# dmo.net
KiCad netlist of a schematic drawn in EAGLE
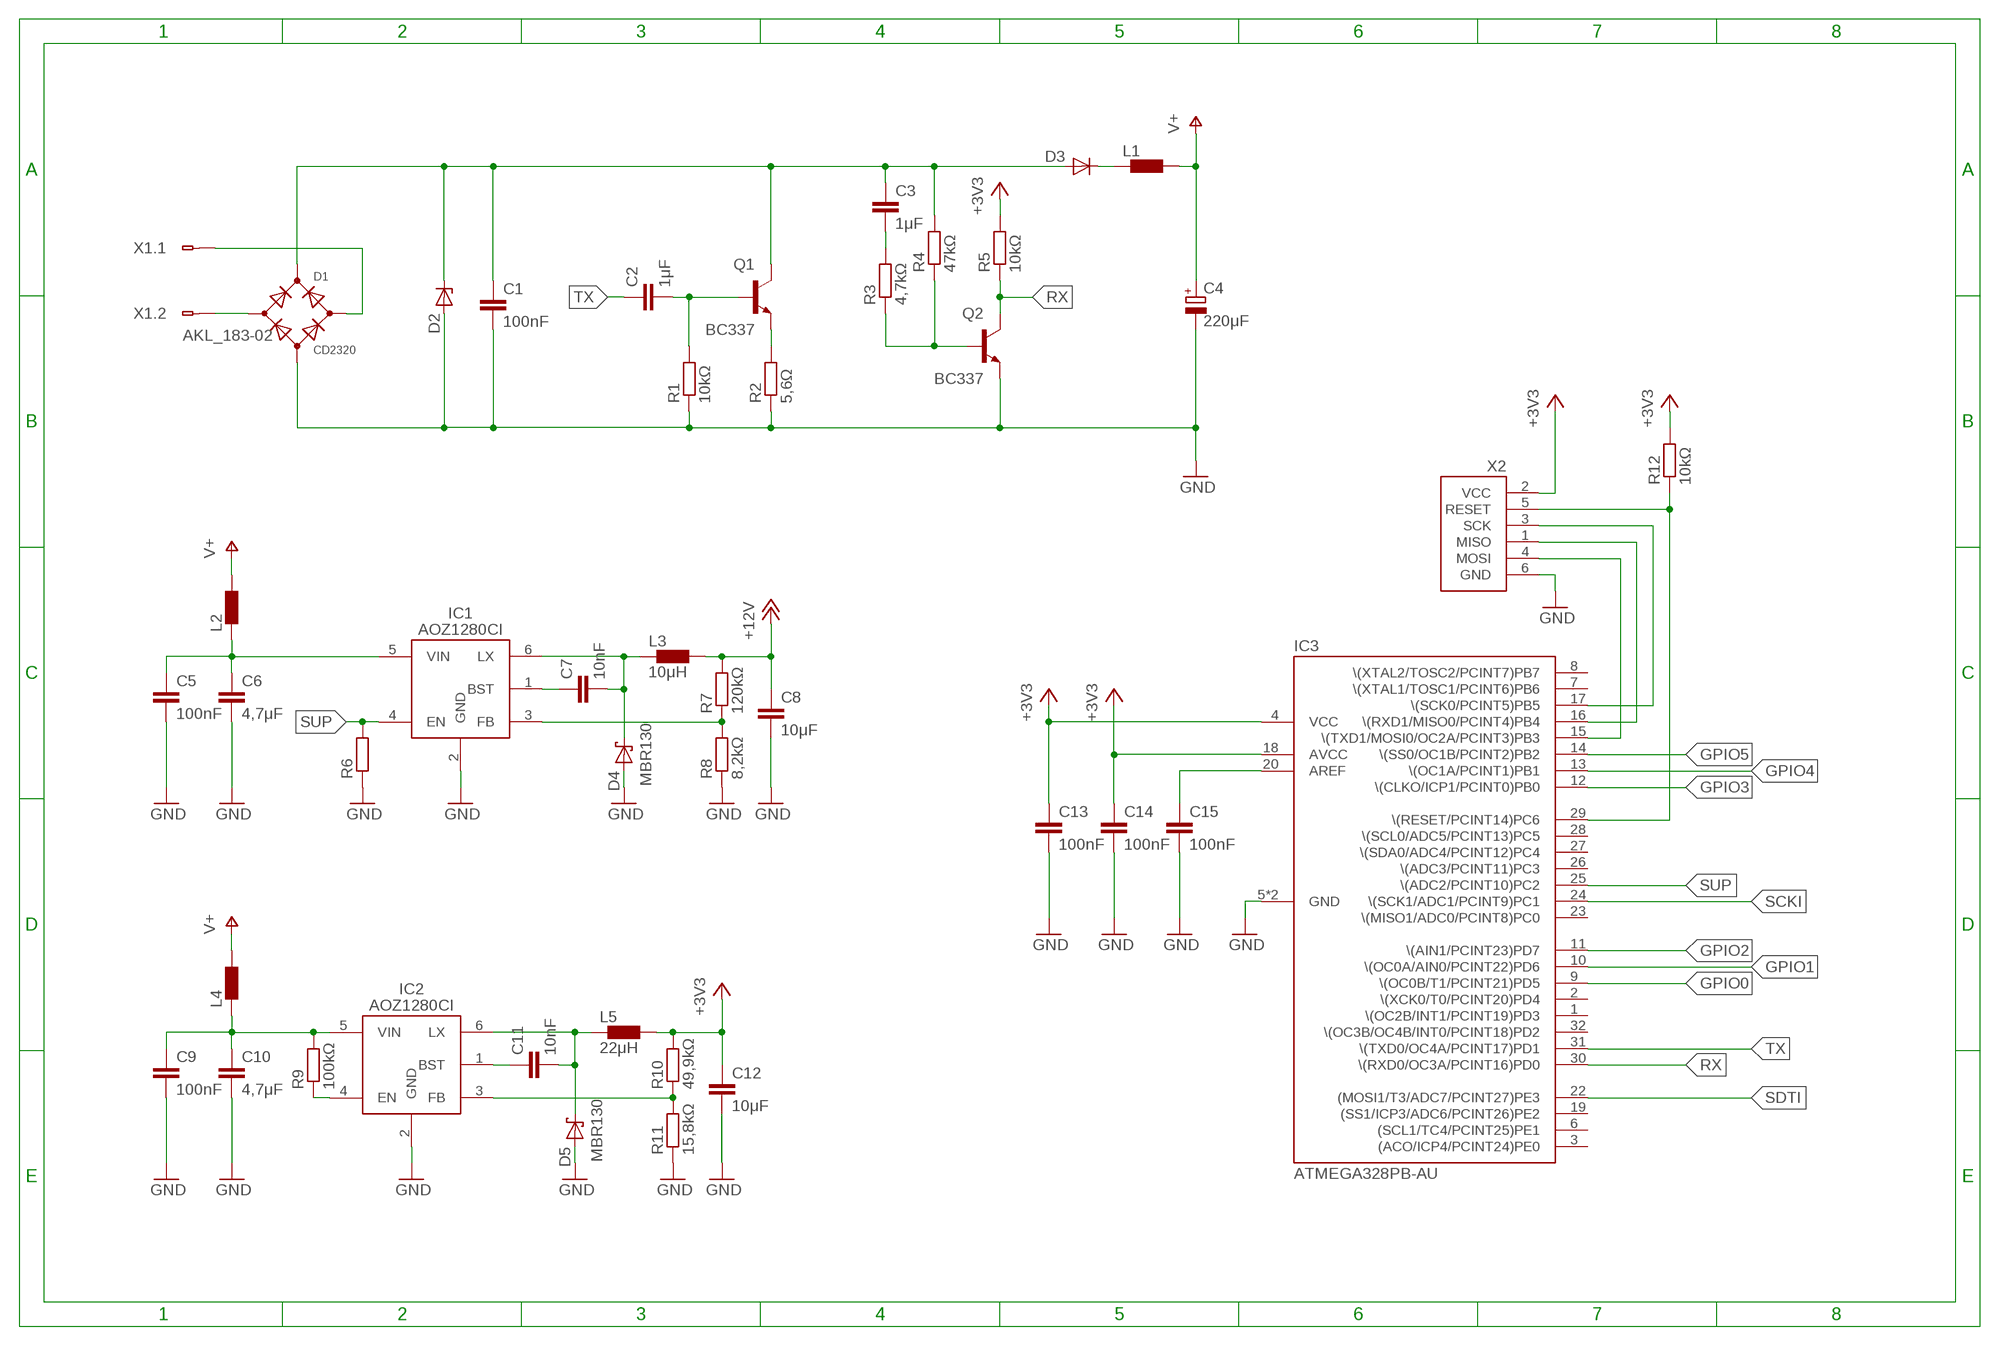
[diagram p0: schematic, sheet 1]

(export (version "E")
  (design (tool "Eeschema 10.0.6"))
  (components
    (comp (ref "C1")
      (value "100nF")
      (footprint "eagle-import:CHIP_1206")
      (libsource (lib "eagle-import") (part "C_1206"))
    )
    (comp (ref "C2")
      (value "1μF")
      (footprint "eagle-import:CHIP_1206")
      (libsource (lib "eagle-import") (part "C_1206"))
    )
    (comp (ref "C3")
      (value "1μF")
      (footprint "eagle-import:CHIP_1206")
      (libsource (lib "eagle-import") (part "C_1206"))
    )
    (comp (ref "C4")
      (value "220μF")
      (footprint "eagle-import:E5-13")
      (libsource (lib "eagle-import") (part "C_EL_E5-13"))
    )
    (comp (ref "C5")
      (value "100nF")
      (footprint "eagle-import:CHIP_0805")
      (libsource (lib "eagle-import") (part "C_0805"))
    )
    (comp (ref "C6")
      (value "4,7μF")
      (footprint "eagle-import:CHIP_1206")
      (libsource (lib "eagle-import") (part "C_1206"))
    )
    (comp (ref "C7")
      (value "10nF")
      (footprint "eagle-import:CHIP_0603")
      (libsource (lib "eagle-import") (part "C_0603"))
    )
    (comp (ref "C8")
      (value "10μF")
      (footprint "eagle-import:CHIP_1206")
      (libsource (lib "eagle-import") (part "C_1206"))
    )
    (comp (ref "C9")
      (value "100nF")
      (footprint "eagle-import:CHIP_0805")
      (libsource (lib "eagle-import") (part "C_0805"))
    )
    (comp (ref "C10")
      (value "4,7μF")
      (footprint "eagle-import:CHIP_1206")
      (libsource (lib "eagle-import") (part "C_1206"))
    )
    (comp (ref "C11")
      (value "10nF")
      (footprint "eagle-import:CHIP_0603")
      (libsource (lib "eagle-import") (part "C_0603"))
    )
    (comp (ref "C12")
      (value "10μF")
      (footprint "eagle-import:CHIP_1206")
      (libsource (lib "eagle-import") (part "C_1206"))
    )
    (comp (ref "C13")
      (value "100nF")
      (footprint "eagle-import:CHIP_0603")
      (libsource (lib "eagle-import") (part "C_0603"))
    )
    (comp (ref "C14")
      (value "100nF")
      (footprint "eagle-import:CHIP_0603")
      (libsource (lib "eagle-import") (part "C_0603"))
    )
    (comp (ref "C15")
      (value "100nF")
      (footprint "eagle-import:CHIP_0603")
      (libsource (lib "eagle-import") (part "C_0603"))
    )
    (comp (ref "D1")
      (value "CD2320")
      (footprint "eagle-import:2320")
      (libsource (lib "eagle-import") (part "CD2320"))
    )
    (comp (ref "D2")
      (value "Z-DIODE-SOD123")
      (footprint "eagle-import:SOD123")
      (libsource (lib "eagle-import") (part "Z-DIODE-SOD123"))
    )
    (comp (ref "D3")
      (value "DIODE-SOD123")
      (footprint "eagle-import:SOD123")
      (libsource (lib "eagle-import") (part "DIODE-SOD123"))
    )
    (comp (ref "D4")
      (value "MBR130")
      (footprint "eagle-import:SOD123")
      (libsource (lib "eagle-import") (part "SHOTKY-DIODE-SOD123"))
    )
    (comp (ref "D5")
      (value "MBR130")
      (footprint "eagle-import:SOD123")
      (libsource (lib "eagle-import") (part "SHOTKY-DIODE-SOD123"))
    )
    (comp (ref "IC1")
      (value "AOZ1280CI")
      (footprint "eagle-import:SOT23-6_095")
      (libsource (lib "eagle-import") (part "AOZ1280CI"))
    )
    (comp (ref "IC2")
      (value "AOZ1280CI")
      (footprint "eagle-import:SOT23-6_095")
      (libsource (lib "eagle-import") (part "AOZ1280CI"))
    )
    (comp (ref "IC3")
      (value "ATMEGA328PB-AU")
      (footprint "eagle-import:QFP32_08")
      (libsource (lib "eagle-import") (part "ATMEGA8PB-AU32"))
    )
    (comp (ref "L1")
      (value "L_0805")
      (footprint "eagle-import:CHIP_0805")
      (libsource (lib "eagle-import") (part "L_0805"))
    )
    (comp (ref "L2")
      (value "L_0805")
      (footprint "eagle-import:CHIP_0805")
      (libsource (lib "eagle-import") (part "L_0805"))
    )
    (comp (ref "L3")
      (value "10μH")
      (footprint "eagle-import:CHIP_1210")
      (libsource (lib "eagle-import") (part "L_1210"))
    )
    (comp (ref "L4")
      (value "L_0805")
      (footprint "eagle-import:CHIP_0805")
      (libsource (lib "eagle-import") (part "L_0805"))
    )
    (comp (ref "L5")
      (value "22μH")
      (footprint "eagle-import:CHIP_0805")
      (libsource (lib "eagle-import") (part "L_0805"))
    )
    (comp (ref "Q1")
      (value "BC337")
      (footprint "eagle-import:SOT23")
      (libsource (lib "eagle-import") (part "NPN-SOT23-BEC"))
    )
    (comp (ref "Q2")
      (value "BC337")
      (footprint "eagle-import:SOT23")
      (libsource (lib "eagle-import") (part "NPN-SOT23-BEC"))
    )
    (comp (ref "R1")
      (value "10kΩ")
      (footprint "eagle-import:CHIP_0603")
      (libsource (lib "eagle-import") (part "R_0603"))
    )
    (comp (ref "R2")
      (value "5,6Ω")
      (footprint "eagle-import:CHIP_1206")
      (libsource (lib "eagle-import") (part "R_1206"))
    )
    (comp (ref "R3")
      (value "4,7kΩ")
      (footprint "eagle-import:CHIP_0603")
      (libsource (lib "eagle-import") (part "R_0603"))
    )
    (comp (ref "R4")
      (value "47kΩ")
      (footprint "eagle-import:CHIP_0603")
      (libsource (lib "eagle-import") (part "R_0603"))
    )
    (comp (ref "R5")
      (value "10kΩ")
      (footprint "eagle-import:CHIP_0603")
      (libsource (lib "eagle-import") (part "R_0603"))
    )
    (comp (ref "R6")
      (value "R_0603")
      (footprint "eagle-import:CHIP_0603")
      (libsource (lib "eagle-import") (part "R_0603"))
    )
    (comp (ref "R7")
      (value "120kΩ")
      (footprint "eagle-import:CHIP_0603")
      (libsource (lib "eagle-import") (part "R_0603"))
    )
    (comp (ref "R8")
      (value "8,2kΩ")
      (footprint "eagle-import:CHIP_0603")
      (libsource (lib "eagle-import") (part "R_0603"))
    )
    (comp (ref "R9")
      (value "100kΩ")
      (footprint "eagle-import:CHIP_0603")
      (libsource (lib "eagle-import") (part "R_0603"))
    )
    (comp (ref "R10")
      (value "49,9kΩ")
      (footprint "eagle-import:CHIP_0603")
      (libsource (lib "eagle-import") (part "R_0603"))
    )
    (comp (ref "R11")
      (value "15,8kΩ")
      (footprint "eagle-import:CHIP_0603")
      (libsource (lib "eagle-import") (part "R_0603"))
    )
    (comp (ref "R12")
      (value "10kΩ")
      (footprint "eagle-import:CHIP_0603")
      (libsource (lib "eagle-import") (part "R_0603"))
    )
    (comp (ref "X1")
      (value "AKL_183-02")
      (footprint "eagle-import:AKL_183-02")
      (libsource (lib "eagle-import") (part "AKL_183-02"))
    )
    (comp (ref "X2")
      (value "ISP-AVR6")
      (footprint "eagle-import:ML6")
      (libsource (lib "eagle-import") (part "ISP-AVR6"))
    )
  )
  (nets
    (net (code "1") (name "+3V3") (class "Default")
      (node (ref "C12") (pin "1") (pinfunction "1_1") (pintype "passive"))
      (node (ref "C13") (pin "1") (pinfunction "1_1") (pintype "passive"))
      (node (ref "C14") (pin "1") (pinfunction "1_1") (pintype "passive"))
      (node (ref "IC3") (pin "18") (pinfunction "AVCC_18") (pintype "power_in"))
      (node (ref "IC3") (pin "4") (pinfunction "VCC_4") (pintype "power_in"))
      (node (ref "L5") (pin "1") (pinfunction "1_1") (pintype "passive"))
      (node (ref "R10") (pin "2") (pinfunction "2_2") (pintype "passive"))
      (node (ref "R12") (pin "2") (pinfunction "2_2") (pintype "passive"))
      (node (ref "R5") (pin "2") (pinfunction "2_2") (pintype "passive"))
      (node (ref "X2") (pin "2") (pinfunction "VCC_2") (pintype "power_in"))
    )
    (net (code "2") (name "+12V") (class "Default")
      (node (ref "C8") (pin "1") (pinfunction "1_1") (pintype "passive"))
      (node (ref "L3") (pin "1") (pinfunction "1_1") (pintype "passive"))
      (node (ref "R7") (pin "2") (pinfunction "2_2") (pintype "passive"))
    )
    (net (code "3") (name "GND") (class "Default")
      (node (ref "C1") (pin "2") (pinfunction "2_2") (pintype "passive"))
      (node (ref "C10") (pin "2") (pinfunction "2_2") (pintype "passive"))
      (node (ref "C12") (pin "2") (pinfunction "2_2") (pintype "passive"))
      (node (ref "C13") (pin "2") (pinfunction "2_2") (pintype "passive"))
      (node (ref "C14") (pin "2") (pinfunction "2_2") (pintype "passive"))
      (node (ref "C15") (pin "2") (pinfunction "2_2") (pintype "passive"))
      (node (ref "C4") (pin "-") (pinfunction "-_-") (pintype "passive"))
      (node (ref "C5") (pin "2") (pinfunction "2_2") (pintype "passive"))
      (node (ref "C6") (pin "2") (pinfunction "2_2") (pintype "passive"))
      (node (ref "C8") (pin "2") (pinfunction "2_2") (pintype "passive"))
      (node (ref "C9") (pin "2") (pinfunction "2_2") (pintype "passive"))
      (node (ref "D1") (pin "-") (pinfunction "-_-") (pintype "passive"))
      (node (ref "D2") (pin "A") (pinfunction "A_A") (pintype "passive"))
      (node (ref "D4") (pin "A") (pinfunction "A_A") (pintype "passive"))
      (node (ref "D5") (pin "A") (pinfunction "A_A") (pintype "passive"))
      (node (ref "IC1") (pin "2") (pinfunction "GND_2") (pintype "power_in"))
      (node (ref "IC2") (pin "2") (pinfunction "GND_2") (pintype "power_in"))
      (node (ref "IC3") (pin "21") (pinfunction "GND_21") (pintype "power_in"))
      (node (ref "IC3") (pin "5") (pinfunction "GND_5") (pintype "power_in"))
      (node (ref "Q2") (pin "2") (pinfunction "E_2") (pintype "passive"))
      (node (ref "R1") (pin "1") (pinfunction "1_1") (pintype "passive"))
      (node (ref "R11") (pin "1") (pinfunction "1_1") (pintype "passive"))
      (node (ref "R2") (pin "1") (pinfunction "1_1") (pintype "passive"))
      (node (ref "R6") (pin "1") (pinfunction "1_1") (pintype "passive"))
      (node (ref "R8") (pin "1") (pinfunction "1_1") (pintype "passive"))
      (node (ref "X2") (pin "6") (pinfunction "GND_6") (pintype "power_in"))
    )
    (net (code "4") (name "GPIO0") (class "Default")
      (node (ref "IC3") (pin "9") (pinfunction "\\(OC0B/T1/PCINT21)PD5_9") (pintype "bidirectional"))
    )
    (net (code "5") (name "GPIO1") (class "Default")
      (node (ref "IC3") (pin "10") (pinfunction "\\(OC0A/AIN0/PCINT22)PD6_10") (pintype "bidirectional"))
    )
    (net (code "6") (name "GPIO2") (class "Default")
      (node (ref "IC3") (pin "11") (pinfunction "\\(AIN1/PCINT23)PD7_11") (pintype "bidirectional"))
    )
    (net (code "7") (name "GPIO3") (class "Default")
      (node (ref "IC3") (pin "12") (pinfunction "\\(CLKO/ICP1/PCINT0)PB0_12") (pintype "bidirectional"))
    )
    (net (code "8") (name "GPIO4") (class "Default")
      (node (ref "IC3") (pin "13") (pinfunction "\\(OC1A/PCINT1)PB1_13") (pintype "bidirectional"))
    )
    (net (code "9") (name "GPIO5") (class "Default")
      (node (ref "IC3") (pin "14") (pinfunction "\\(SS0/OC1B/PCINT2)PB2_14") (pintype "bidirectional"))
    )
    (net (code "10") (name "Net-(C3-Pad2)") (class "Default")
      (node (ref "C3") (pin "2") (pinfunction "2_2") (pintype "passive"))
      (node (ref "R3") (pin "2") (pinfunction "2_2") (pintype "passive"))
    )
    (net (code "11") (name "Net-(D3-PadK)") (class "Default")
      (node (ref "D3") (pin "K") (pinfunction "K_K") (pintype "passive"))
      (node (ref "L1") (pin "2") (pinfunction "2_2") (pintype "passive"))
    )
    (net (code "12") (name "Net-(IC1-BST)") (class "Default")
      (node (ref "C7") (pin "1") (pinfunction "1_1") (pintype "passive"))
      (node (ref "IC1") (pin "1") (pinfunction "BST_1") (pintype "bidirectional"))
    )
    (net (code "13") (name "Net-(IC1-FB)") (class "Default")
      (node (ref "IC1") (pin "3") (pinfunction "FB_3") (pintype "input"))
      (node (ref "R7") (pin "1") (pinfunction "1_1") (pintype "passive"))
      (node (ref "R8") (pin "2") (pinfunction "2_2") (pintype "passive"))
    )
    (net (code "14") (name "Net-(IC1-LX)") (class "Default")
      (node (ref "C7") (pin "2") (pinfunction "2_2") (pintype "passive"))
      (node (ref "D4") (pin "K") (pinfunction "K_K") (pintype "passive"))
      (node (ref "IC1") (pin "6") (pinfunction "LX_6") (pintype "output"))
      (node (ref "L3") (pin "2") (pinfunction "2_2") (pintype "passive"))
    )
    (net (code "15") (name "Net-(IC1-VIN)") (class "Default")
      (node (ref "C5") (pin "1") (pinfunction "1_1") (pintype "passive"))
      (node (ref "C6") (pin "1") (pinfunction "1_1") (pintype "passive"))
      (node (ref "IC1") (pin "5") (pinfunction "VIN_5") (pintype "power_in"))
      (node (ref "L2") (pin "2") (pinfunction "2_2") (pintype "passive"))
    )
    (net (code "16") (name "Net-(IC2-BST)") (class "Default")
      (node (ref "C11") (pin "1") (pinfunction "1_1") (pintype "passive"))
      (node (ref "IC2") (pin "1") (pinfunction "BST_1") (pintype "bidirectional"))
    )
    (net (code "17") (name "Net-(IC2-EN)") (class "Default")
      (node (ref "IC2") (pin "4") (pinfunction "EN_4") (pintype "input"))
      (node (ref "R9") (pin "1") (pinfunction "1_1") (pintype "passive"))
    )
    (net (code "18") (name "Net-(IC2-FB)") (class "Default")
      (node (ref "IC2") (pin "3") (pinfunction "FB_3") (pintype "input"))
      (node (ref "R10") (pin "1") (pinfunction "1_1") (pintype "passive"))
      (node (ref "R11") (pin "2") (pinfunction "2_2") (pintype "passive"))
    )
    (net (code "19") (name "Net-(IC2-LX)") (class "Default")
      (node (ref "C11") (pin "2") (pinfunction "2_2") (pintype "passive"))
      (node (ref "D5") (pin "K") (pinfunction "K_K") (pintype "passive"))
      (node (ref "IC2") (pin "6") (pinfunction "LX_6") (pintype "output"))
      (node (ref "L5") (pin "2") (pinfunction "2_2") (pintype "passive"))
    )
    (net (code "20") (name "Net-(IC2-VIN)") (class "Default")
      (node (ref "C10") (pin "1") (pinfunction "1_1") (pintype "passive"))
      (node (ref "C9") (pin "1") (pinfunction "1_1") (pintype "passive"))
      (node (ref "IC2") (pin "5") (pinfunction "VIN_5") (pintype "power_in"))
      (node (ref "L4") (pin "2") (pinfunction "2_2") (pintype "passive"))
      (node (ref "R9") (pin "2") (pinfunction "2_2") (pintype "passive"))
    )
    (net (code "21") (name "Net-(IC3-AREF)") (class "Default")
      (node (ref "C15") (pin "1") (pinfunction "1_1") (pintype "passive"))
      (node (ref "IC3") (pin "20") (pinfunction "AREF_20") (pintype "passive"))
    )
    (net (code "22") (name "Net-(IC3-\\(RESET{slash}PCINT14)PC6)") (class "Default")
      (node (ref "IC3") (pin "29") (pinfunction "\\(RESET/PCINT14)PC6_29") (pintype "bidirectional"))
      (node (ref "R12") (pin "1") (pinfunction "1_1") (pintype "passive"))
      (node (ref "X2") (pin "5") (pinfunction "RESET_5") (pintype "passive"))
    )
    (net (code "23") (name "Net-(IC3-\\(RXD1{slash}MISO0{slash}PCINT4)PB4)") (class "Default")
      (node (ref "IC3") (pin "16") (pinfunction "\\(RXD1/MISO0/PCINT4)PB4_16") (pintype "bidirectional"))
      (node (ref "X2") (pin "1") (pinfunction "MISO_1") (pintype "passive"))
    )
    (net (code "24") (name "Net-(IC3-\\(SCK0{slash}PCINT5)PB5)") (class "Default")
      (node (ref "IC3") (pin "17") (pinfunction "\\(SCK0/PCINT5)PB5_17") (pintype "bidirectional"))
      (node (ref "X2") (pin "3") (pinfunction "SCK_3") (pintype "passive"))
    )
    (net (code "25") (name "Net-(IC3-\\(TXD1{slash}MOSI0{slash}OC2A{slash}PCINT3)PB3)") (class "Default")
      (node (ref "IC3") (pin "15") (pinfunction "\\(TXD1/MOSI0/OC2A/PCINT3)PB3_15") (pintype "bidirectional"))
      (node (ref "X2") (pin "4") (pinfunction "MOSI_4") (pintype "passive"))
    )
    (net (code "26") (name "Net-(Q1-B)") (class "Default")
      (node (ref "C2") (pin "2") (pinfunction "2_2") (pintype "passive"))
      (node (ref "Q1") (pin "1") (pinfunction "B_1") (pintype "passive"))
      (node (ref "R1") (pin "2") (pinfunction "2_2") (pintype "passive"))
    )
    (net (code "27") (name "Net-(Q1-C)") (class "Default")
      (node (ref "C1") (pin "1") (pinfunction "1_1") (pintype "passive"))
      (node (ref "C3") (pin "1") (pinfunction "1_1") (pintype "passive"))
      (node (ref "D1") (pin "+") (pinfunction "+_+") (pintype "passive"))
      (node (ref "D2") (pin "K") (pinfunction "K_K") (pintype "passive"))
      (node (ref "D3") (pin "A") (pinfunction "A_A") (pintype "passive"))
      (node (ref "Q1") (pin "3") (pinfunction "C_3") (pintype "passive"))
      (node (ref "R4") (pin "2") (pinfunction "2_2") (pintype "passive"))
    )
    (net (code "28") (name "Net-(Q1-E)") (class "Default")
      (node (ref "Q1") (pin "2") (pinfunction "E_2") (pintype "passive"))
      (node (ref "R2") (pin "2") (pinfunction "2_2") (pintype "passive"))
    )
    (net (code "29") (name "Net-(Q2-B)") (class "Default")
      (node (ref "Q2") (pin "1") (pinfunction "B_1") (pintype "passive"))
      (node (ref "R3") (pin "1") (pinfunction "1_1") (pintype "passive"))
      (node (ref "R4") (pin "1") (pinfunction "1_1") (pintype "passive"))
    )
    (net (code "30") (name "Net-(X1A-A)") (class "Default")
      (node (ref "D1") (pin "AC2") (pinfunction "AC2_AC2") (pintype "passive"))
      (node (ref "X1") (pin "1") (pinfunction "A_1") (pintype "passive"))
    )
    (net (code "31") (name "Net-(X1B-A)") (class "Default")
      (node (ref "D1") (pin "AC1") (pinfunction "AC1_AC1") (pintype "passive"))
      (node (ref "X1") (pin "2") (pinfunction "A_2") (pintype "passive"))
    )
    (net (code "32") (name "RX") (class "Default")
      (node (ref "IC3") (pin "30") (pinfunction "\\(RXD0/OC3A/PCINT16)PD0_30") (pintype "bidirectional"))
      (node (ref "Q2") (pin "3") (pinfunction "C_3") (pintype "passive"))
      (node (ref "R5") (pin "1") (pinfunction "1_1") (pintype "passive"))
    )
    (net (code "33") (name "SCKI") (class "Default")
      (node (ref "IC3") (pin "24") (pinfunction "\\(SCK1/ADC1/PCINT9)PC1_24") (pintype "bidirectional"))
    )
    (net (code "34") (name "SDTI") (class "Default")
      (node (ref "IC3") (pin "22") (pinfunction "(MOSI1/T3/ADC7/PCINT27)PE3_22") (pintype "bidirectional"))
    )
    (net (code "35") (name "SUP") (class "Default")
      (node (ref "IC1") (pin "4") (pinfunction "EN_4") (pintype "input"))
      (node (ref "IC3") (pin "25") (pinfunction "\\(ADC2/PCINT10)PC2_25") (pintype "bidirectional"))
      (node (ref "R6") (pin "2") (pinfunction "2_2") (pintype "passive"))
    )
    (net (code "36") (name "TX") (class "Default")
      (node (ref "C2") (pin "1") (pinfunction "1_1") (pintype "passive"))
      (node (ref "IC3") (pin "31") (pinfunction "\\(TXD0/OC4A/PCINT17)PD1_31") (pintype "bidirectional"))
    )
    (net (code "37") (name "V+") (class "Default")
      (node (ref "C4") (pin "+") (pinfunction "+_+") (pintype "passive"))
      (node (ref "L1") (pin "1") (pinfunction "1_1") (pintype "passive"))
      (node (ref "L2") (pin "1") (pinfunction "1_1") (pintype "passive"))
      (node (ref "L4") (pin "1") (pinfunction "1_1") (pintype "passive"))
    )
    (net (code "38") (name "unconnected-(IC3-(ACO{slash}ICP4{slash}PCINT24)PE0-Pad3)") (class "Default")
      (node (ref "IC3") (pin "3") (pinfunction "(ACO/ICP4/PCINT24)PE0_3") (pintype "bidirectional"))
    )
    (net (code "39") (name "unconnected-(IC3-(SCL1{slash}TC4{slash}PCINT25)PE1-Pad6)") (class "Default")
      (node (ref "IC3") (pin "6") (pinfunction "(SCL1/TC4/PCINT25)PE1_6") (pintype "bidirectional"))
    )
    (net (code "40") (name "unconnected-(IC3-(SS1{slash}ICP3{slash}ADC6{slash}PCINT26)PE2-Pad19)") (class "Default")
      (node (ref "IC3") (pin "19") (pinfunction "(SS1/ICP3/ADC6/PCINT26)PE2_19") (pintype "bidirectional"))
    )
    (net (code "41") (name "unconnected-(IC3-\\(ADC3{slash}PCINT11)PC3-Pad26)") (class "Default")
      (node (ref "IC3") (pin "26") (pinfunction "\\(ADC3/PCINT11)PC3_26") (pintype "bidirectional"))
    )
    (net (code "42") (name "unconnected-(IC3-\\(MISO1{slash}ADC0{slash}PCINT8)PC0-Pad23)") (class "Default")
      (node (ref "IC3") (pin "23") (pinfunction "\\(MISO1/ADC0/PCINT8)PC0_23") (pintype "bidirectional"))
    )
    (net (code "43") (name "unconnected-(IC3-\\(OC2B{slash}INT1{slash}PCINT19)PD3-Pad1)") (class "Default")
      (node (ref "IC3") (pin "1") (pinfunction "\\(OC2B/INT1/PCINT19)PD3_1") (pintype "bidirectional"))
    )
    (net (code "44") (name "unconnected-(IC3-\\(OC3B{slash}OC4B{slash}INT0{slash}PCINT18)PD2-Pad32)") (class "Default")
      (node (ref "IC3") (pin "32") (pinfunction "\\(OC3B/OC4B/INT0/PCINT18)PD2_32") (pintype "bidirectional"))
    )
    (net (code "45") (name "unconnected-(IC3-\\(SCL0{slash}ADC5{slash}PCINT13)PC5-Pad28)") (class "Default")
      (node (ref "IC3") (pin "28") (pinfunction "\\(SCL0/ADC5/PCINT13)PC5_28") (pintype "bidirectional"))
    )
    (net (code "46") (name "unconnected-(IC3-\\(SDA0{slash}ADC4{slash}PCINT12)PC4-Pad27)") (class "Default")
      (node (ref "IC3") (pin "27") (pinfunction "\\(SDA0/ADC4/PCINT12)PC4_27") (pintype "bidirectional"))
    )
    (net (code "47") (name "unconnected-(IC3-\\(XCK0{slash}T0{slash}PCINT20)PD4-Pad2)") (class "Default")
      (node (ref "IC3") (pin "2") (pinfunction "\\(XCK0/T0/PCINT20)PD4_2") (pintype "bidirectional"))
    )
    (net (code "48") (name "unconnected-(IC3-\\(XTAL1{slash}TOSC1{slash}PCINT6)PB6-Pad7)") (class "Default")
      (node (ref "IC3") (pin "7") (pinfunction "\\(XTAL1/TOSC1/PCINT6)PB6_7") (pintype "bidirectional"))
    )
    (net (code "49") (name "unconnected-(IC3-\\(XTAL2{slash}TOSC2{slash}PCINT7)PB7-Pad8)") (class "Default")
      (node (ref "IC3") (pin "8") (pinfunction "\\(XTAL2/TOSC2/PCINT7)PB7_8") (pintype "bidirectional"))
    )
  )
)
